# Alimentations.net
KiCad netlist of a schematic drawn in Altium Designer
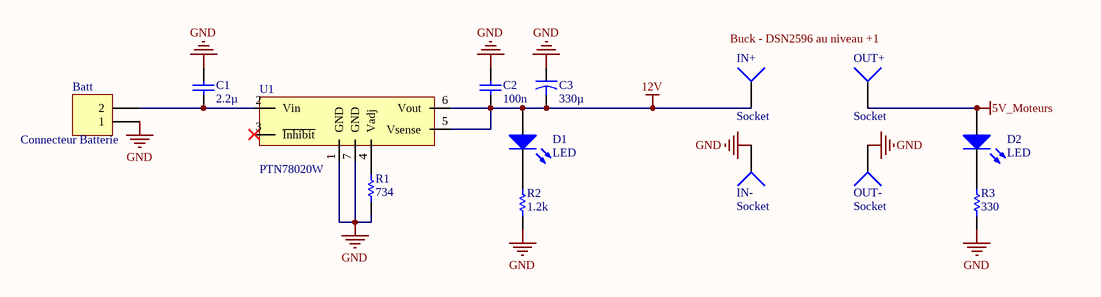
[diagram p0: Alimentations.SchDoc]

(export (version "E")
  (design (tool "Eeschema 10.0.6"))
  (components
    (comp (ref "Batt")
      (value "Connecteur Batterie")
      (footprint "SHDR2W95P0X381_1X2_901X700X940P")
      (description "Header, 2-Pin")
      (fields (field (name "PUBLISHER") "Altium Limited"))
      (libsource (lib "Miscellaneous Connectors") (part "Header 2"))
    )
    (comp (ref "C1")
      (value "2.2µ")
      (footprint "0805")
      (fields (field (name "Comment") "Cap") (field (name "PUBLISHER") "Altium Limited"))
      (libsource (lib "Miscellaneous Devices") (part "Cap"))
    )
    (comp (ref "C2")
      (value "100n")
      (footprint "0805")
      (fields (field (name "Comment") "Cap") (field (name "PUBLISHER") "Altium Limited"))
      (libsource (lib "Miscellaneous Devices") (part "Cap"))
    )
    (comp (ref "C3")
      (value "330µ")
      (footprint "CAPR5-4X5")
      (fields (field (name "Comment") "Cap2") (field (name "PUBLISHER") "Altium Limited"))
      (libsource (lib "Miscellaneous Devices") (part "Cap2"))
    )
    (comp (ref "D1")
      (value "LED")
      (footprint "C0805")
      (description "LED Bleu")
      (fields (field (name "PUBLISHER") "Altium Limited"))
      (libsource (lib "Miscellaneous Devices") (part "LED1"))
    )
    (comp (ref "D2")
      (value "LED")
      (footprint "C0805")
      (description "LED Verte")
      (fields (field (name "PUBLISHER") "Altium Limited"))
      (libsource (lib "Miscellaneous Devices") (part "LED1"))
    )
    (comp (ref "IN+")
      (value "Socket")
      (footprint "PIN1")
      (fields (field (name "PUBLISHER") "Altium Limited"))
      (libsource (lib "Miscellaneous Connectors") (part "Socket"))
    )
    (comp (ref "IN-")
      (value "Socket")
      (footprint "PIN1")
      (fields (field (name "PUBLISHER") "Altium Limited"))
      (libsource (lib "Miscellaneous Connectors") (part "Socket"))
    )
    (comp (ref "OUT+")
      (value "Socket")
      (footprint "PIN1")
      (fields (field (name "PUBLISHER") "Altium Limited"))
      (libsource (lib "Miscellaneous Connectors") (part "Socket"))
    )
    (comp (ref "OUT-")
      (value "Socket")
      (footprint "PIN1")
      (fields (field (name "PUBLISHER") "Altium Limited"))
      (libsource (lib "Miscellaneous Connectors") (part "Socket"))
    )
    (comp (ref "R1")
      (value "734")
      (footprint "0805")
      (description "734R 1%")
      (fields (field (name "Comment") "Res*") (field (name "PUBLISHER") "Altium Limited"))
      (libsource (lib "Miscellaneous Devices") (part "Res*"))
    )
    (comp (ref "R2")
      (value "1.2k")
      (footprint "0805")
      (fields (field (name "Comment") "Res*") (field (name "PUBLISHER") "Altium Limited"))
      (libsource (lib "Miscellaneous Devices") (part "Res*"))
    )
    (comp (ref "R3")
      (value "330")
      (footprint "0805")
      (description "330R")
      (fields (field (name "Comment") "Res*") (field (name "PUBLISHER") "Altium Limited"))
      (libsource (lib "Miscellaneous Devices") (part "Res*"))
    )
    (comp (ref "U1")
      (value "PTN78020W")
      (footprint "PTN78020WAH")
      (description "Alim à découpage 6A")
      (libsource (lib "lib_Gabriel") (part "PTN78020W"))
    )
  )
  (nets
    (net (code "2") (name "5V_Moteurs") (class "Default")
      (node (ref "D2") (pin "1") (pinfunction "A_1") (pintype "passive"))
      (node (ref "OUT+") (pin "1") (pinfunction "1_1") (pintype "passive"))
    )
    (net (code "3") (name "12V") (class "Default")
      (node (ref "C2") (pin "1") (pinfunction "1_1") (pintype "passive"))
      (node (ref "C3") (pin "2") (pinfunction "2_2") (pintype "passive"))
      (node (ref "D1") (pin "1") (pinfunction "A_1") (pintype "passive"))
      (node (ref "IN+") (pin "1") (pinfunction "1_1") (pintype "passive"))
      (node (ref "U1") (pin "5") (pinfunction "Vsense_5") (pintype "passive"))
      (node (ref "U1") (pin "6") (pinfunction "Vout_6") (pintype "passive"))
    )
    (net (code "4") (name "GND") (class "Default")
      (node (ref "Batt") (pin "1") (pinfunction "1_1") (pintype "passive"))
      (node (ref "C1") (pin "2") (pinfunction "2_2") (pintype "passive"))
      (node (ref "C2") (pin "2") (pinfunction "2_2") (pintype "passive"))
      (node (ref "C3") (pin "1") (pinfunction "1_1") (pintype "passive"))
      (node (ref "IN-") (pin "1") (pinfunction "1_1") (pintype "passive"))
      (node (ref "OUT-") (pin "1") (pinfunction "1_1") (pintype "passive"))
      (node (ref "R1") (pin "1") (pinfunction "1_1") (pintype "passive"))
      (node (ref "R2") (pin "1") (pinfunction "1_1") (pintype "passive"))
      (node (ref "R3") (pin "2") (pinfunction "2_2") (pintype "passive"))
      (node (ref "U1") (pin "1") (pinfunction "GND_1") (pintype "passive"))
      (node (ref "U1") (pin "7") (pinfunction "GND_7") (pintype "passive"))
    )
    (net (code "5") (name "Net-(D1-K)") (class "Default")
      (node (ref "D1") (pin "2") (pinfunction "K_2") (pintype "passive"))
      (node (ref "R2") (pin "2") (pinfunction "2_2") (pintype "passive"))
    )
    (net (code "6") (name "Net-(D2-K)") (class "Default")
      (node (ref "D2") (pin "2") (pinfunction "K_2") (pintype "passive"))
      (node (ref "R3") (pin "1") (pinfunction "1_1") (pintype "passive"))
    )
    (net (code "7") (name "Net-(U1-Vadj)") (class "Default")
      (node (ref "R1") (pin "2") (pinfunction "2_2") (pintype "passive"))
      (node (ref "U1") (pin "4") (pinfunction "Vadj_4") (pintype "passive"))
    )
    (net (code "8") (name "Net-(U1-Vin)") (class "Default")
      (node (ref "Batt") (pin "2") (pinfunction "2_2") (pintype "passive"))
      (node (ref "C1") (pin "1") (pinfunction "1_1") (pintype "passive"))
      (node (ref "U1") (pin "2") (pinfunction "Vin_2") (pintype "passive"))
    )
    (net (code "9") (name "unconnected-(U1-Inhibit-Pad3)") (class "Default")
      (node (ref "U1") (pin "3") (pinfunction "Inhibit_3") (pintype "passive+no_connect"))
    )
  )
)
